# Sheet2.net
KiCad netlist of a schematic drawn in Altium Designer
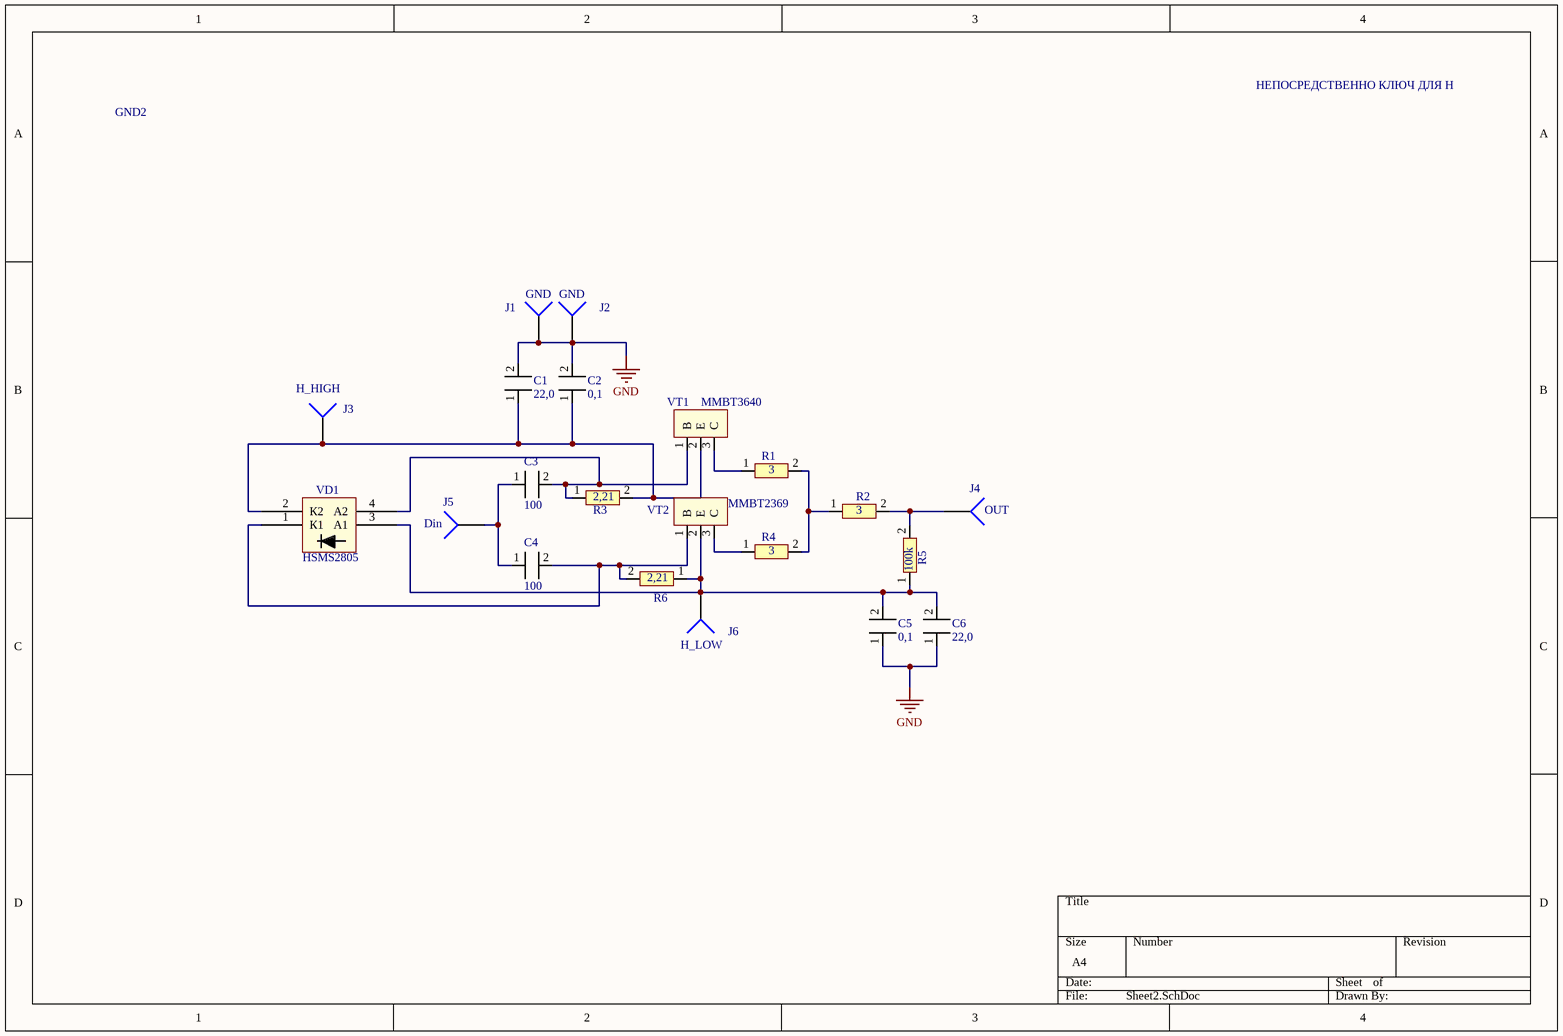
[diagram p0: Sheet2.SchDoc]

(export (version "E")
  (design (tool "Eeschema 10.0.6"))
  (components
    (comp (ref "C1") (value "22,0") (footprint "Cap_BIG") (libsource (lib "Schlib") (part "CAP_BIG")))
    (comp (ref "C2") (value "0,1") (footprint "CAP_SMALL") (libsource (lib "Schlib") (part "CAP_SMALL")))
    (comp (ref "C3") (value "100") (footprint "CAP_SMALL") (libsource (lib "Schlib") (part "CAP_SMALL")))
    (comp (ref "C4") (value "100") (footprint "CAP_SMALL") (libsource (lib "Schlib") (part "CAP_SMALL")))
    (comp (ref "C5") (value "0,1") (footprint "CAP_SMALL") (libsource (lib "Schlib") (part "CAP_SMALL")))
    (comp (ref "C6") (value "22,0") (footprint "Cap_BIG") (libsource (lib "Schlib") (part "CAP_BIG")))
    (comp (ref "J1")
      (value "GND")
      (footprint "PIN1")
      (description "Socket")
      (fields (field (name "PUBLISHER") "Altium Limited"))
      (libsource (lib "Miscellaneous Connectors") (part "Socket"))
    )
    (comp (ref "J2")
      (value "GND")
      (footprint "PIN1")
      (description "Socket")
      (fields (field (name "PUBLISHER") "Altium Limited"))
      (libsource (lib "Miscellaneous Connectors") (part "Socket"))
    )
    (comp (ref "J3")
      (value "H_HIGH")
      (footprint "PIN1")
      (description "Socket")
      (fields (field (name "PUBLISHER") "Altium Limited"))
      (libsource (lib "Miscellaneous Connectors") (part "Socket"))
    )
    (comp (ref "J4")
      (value "OUT")
      (footprint "PIN1")
      (description "Socket")
      (fields (field (name "PUBLISHER") "Altium Limited"))
      (libsource (lib "Miscellaneous Connectors") (part "Socket"))
    )
    (comp (ref "J5")
      (value "Din")
      (footprint "PIN1")
      (description "Socket")
      (fields (field (name "PUBLISHER") "Altium Limited"))
      (libsource (lib "Miscellaneous Connectors") (part "Socket"))
    )
    (comp (ref "J6")
      (value "H_LOW")
      (footprint "PIN1")
      (description "Socket")
      (fields (field (name "PUBLISHER") "Altium Limited"))
      (libsource (lib "Miscellaneous Connectors") (part "Socket"))
    )
    (comp (ref "R1") (value "3") (footprint "RES") (libsource (lib "Schlib") (part "RES")))
    (comp (ref "R2") (value "3") (footprint "RES") (libsource (lib "Schlib") (part "RES")))
    (comp (ref "R3") (value "2,21") (footprint "RES") (libsource (lib "Schlib") (part "RES")))
    (comp (ref "R4") (value "3") (footprint "RES") (libsource (lib "Schlib") (part "RES")))
    (comp (ref "R5") (value "100k") (footprint "RES") (libsource (lib "") (part "RES_2")))
    (comp (ref "R6") (value "2,21") (footprint "RES") (libsource (lib "") (part "RES_1")))
    (comp (ref "VD1") (value "HSMS2805") (footprint "SOT-143B") (libsource (lib "Schlib") (part "HSMS-2805")))
    (comp (ref "VT1")
      (value "MMBT3640")
      (footprint "SOT23-BEC_MMBT3640*(Primary)")
      (libsource (lib "Schlib") (part "MMBT3640"))
    )
    (comp (ref "VT2")
      (value "MMBT2369")
      (footprint "SOT23-BEC_MMBT3640*(Primary)")
      (libsource (lib "Schlib") (part "MMBT2369"))
    )
  )
  (nets
    (net (code "1") (name "GND") (class "Default")
      (node (ref "C1") (pin "2") (pinfunction "2_2") (pintype "passive"))
      (node (ref "C2") (pin "2") (pinfunction "2_2") (pintype "passive"))
      (node (ref "C5") (pin "1") (pinfunction "1_1") (pintype "passive"))
      (node (ref "C6") (pin "1") (pinfunction "1_1") (pintype "passive"))
      (node (ref "J1") (pin "1") (pinfunction "1_1") (pintype "passive"))
      (node (ref "J2") (pin "1") (pinfunction "1_1") (pintype "passive"))
    )
    (net (code "2") (name "Net-(C3-Pad1)") (class "Default")
      (node (ref "C3") (pin "1") (pinfunction "1_1") (pintype "passive"))
      (node (ref "C4") (pin "1") (pinfunction "1_1") (pintype "passive"))
      (node (ref "J5") (pin "1") (pinfunction "1_1") (pintype "passive"))
    )
    (net (code "3") (name "Net-(J4-Pad1)") (class "Default")
      (node (ref "J4") (pin "1") (pinfunction "1_1") (pintype "passive"))
      (node (ref "R2") (pin "2") (pinfunction "2_2") (pintype "passive"))
      (node (ref "R5") (pin "2") (pinfunction "2_2") (pintype "passive"))
    )
    (net (code "4") (name "Net-(R1-Pad2)") (class "Default")
      (node (ref "R1") (pin "2") (pinfunction "2_2") (pintype "passive"))
      (node (ref "R2") (pin "1") (pinfunction "1_1") (pintype "passive"))
      (node (ref "R4") (pin "2") (pinfunction "2_2") (pintype "passive"))
    )
    (net (code "5") (name "Net-(VD1-А1)") (class "Default")
      (node (ref "C5") (pin "2") (pinfunction "2_2") (pintype "passive"))
      (node (ref "C6") (pin "2") (pinfunction "2_2") (pintype "passive"))
      (node (ref "J6") (pin "1") (pinfunction "1_1") (pintype "passive"))
      (node (ref "R5") (pin "1") (pinfunction "1_1") (pintype "passive"))
      (node (ref "R6") (pin "1") (pinfunction "1_1") (pintype "passive"))
      (node (ref "VD1") (pin "3") (pinfunction "А1_3") (pintype "passive"))
      (node (ref "VT2") (pin "2") (pinfunction "E_2") (pintype "passive"))
    )
    (net (code "6") (name "Net-(VD1-А2)") (class "Default")
      (node (ref "C3") (pin "2") (pinfunction "2_2") (pintype "passive"))
      (node (ref "R3") (pin "1") (pinfunction "1_1") (pintype "passive"))
      (node (ref "VD1") (pin "4") (pinfunction "А2_4") (pintype "passive"))
      (node (ref "VT1") (pin "1") (pinfunction "B_1") (pintype "passive"))
    )
    (net (code "7") (name "Net-(VD1-К1)") (class "Default")
      (node (ref "C4") (pin "2") (pinfunction "2_2") (pintype "passive"))
      (node (ref "R6") (pin "2") (pinfunction "2_2") (pintype "passive"))
      (node (ref "VD1") (pin "1") (pinfunction "К1_1") (pintype "passive"))
      (node (ref "VT2") (pin "1") (pinfunction "B_1") (pintype "passive"))
    )
    (net (code "8") (name "Net-(VD1-К2)") (class "Default")
      (node (ref "C1") (pin "1") (pinfunction "1_1") (pintype "passive"))
      (node (ref "C2") (pin "1") (pinfunction "1_1") (pintype "passive"))
      (node (ref "J3") (pin "1") (pinfunction "1_1") (pintype "passive"))
      (node (ref "R3") (pin "2") (pinfunction "2_2") (pintype "passive"))
      (node (ref "VD1") (pin "2") (pinfunction "К2_2") (pintype "passive"))
      (node (ref "VT1") (pin "2") (pinfunction "E_2") (pintype "passive"))
    )
    (net (code "9") (name "Net-(VT1-C)") (class "Default")
      (node (ref "R1") (pin "1") (pinfunction "1_1") (pintype "passive"))
      (node (ref "VT1") (pin "3") (pinfunction "C_3") (pintype "passive"))
    )
    (net (code "10") (name "Net-(VT2-C)") (class "Default")
      (node (ref "R4") (pin "1") (pinfunction "1_1") (pintype "passive"))
      (node (ref "VT2") (pin "3") (pinfunction "C_3") (pintype "passive"))
    )
  )
)
